# Alim.net
KiCad netlist of a schematic drawn in Altium Designer
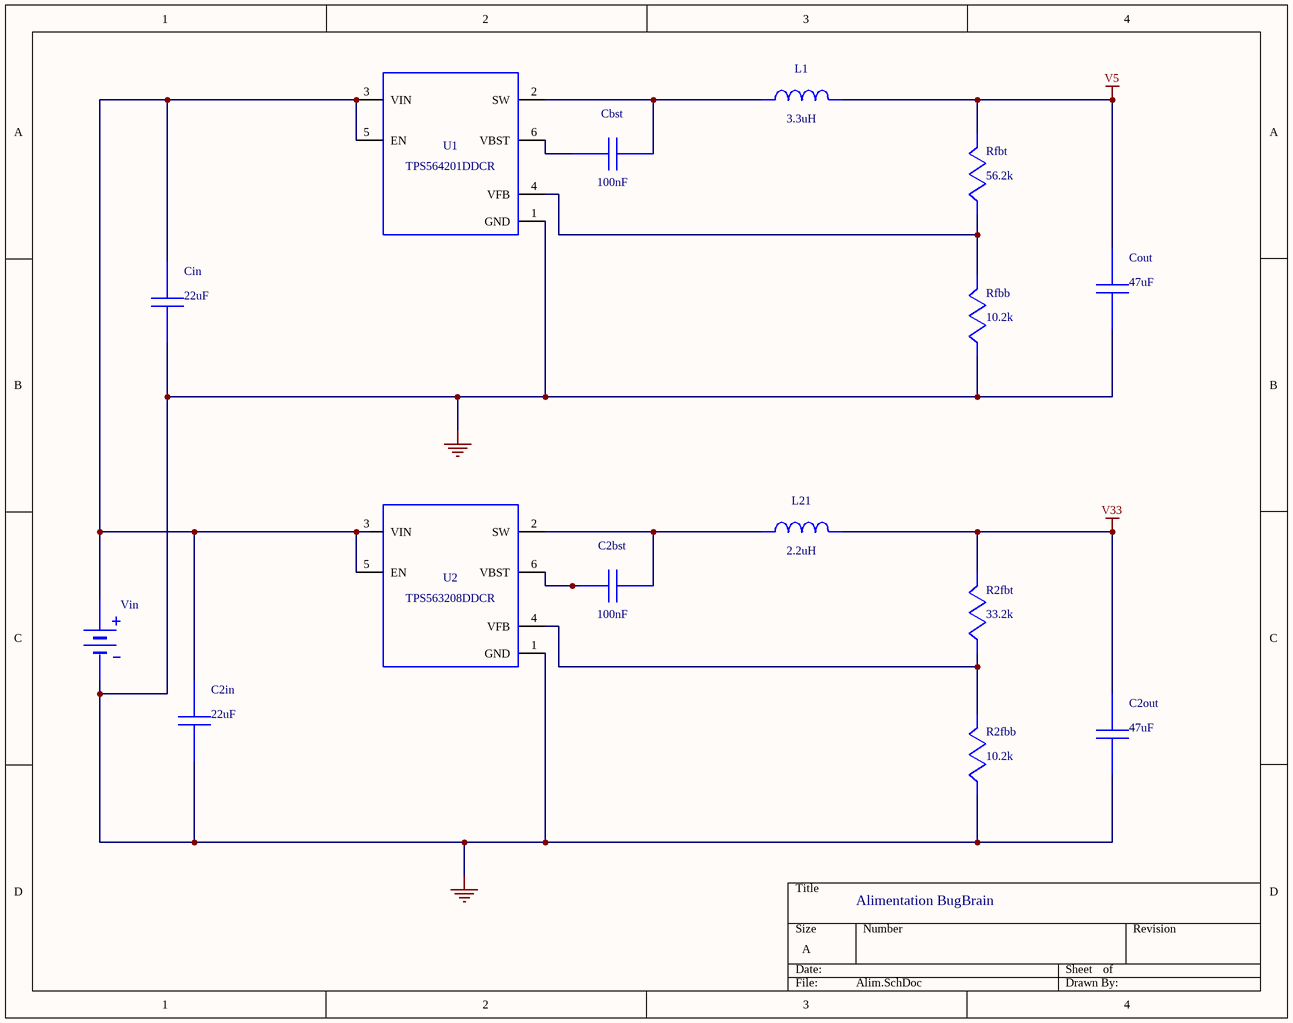
[diagram p0: Alim.SchDoc]

(export (version "E")
  (design (tool "Eeschema 10.0.6"))
  (components
    (comp (ref "C2bst")
      (value "100nF")
      (description "C0805C104K3RACTU")
      (libsource (lib "TI WEBENCH") (part "Cbst"))
    )
    (comp (ref "C2in")
      (value "22uF")
      (description "GRM32ER61E226KE1")
      (fields (field (name "MANUFACTURER PART NUMBER") "GRM32ER61E226KE15L"))
      (libsource (lib "TI WEBENCH") (part "Cin"))
    )
    (comp (ref "C2out")
      (value "47uF")
      (description "C3216X5R1E476M16")
      (fields (field (name "MANUFACTURER PART NUMBER") "C3216X5R1E476M160AC"))
      (libsource (lib "TI WEBENCH") (part "Cout"))
    )
    (comp (ref "Cbst")
      (value "100nF")
      (description "C0805C104K3RACTU")
      (libsource (lib "TI WEBENCH") (part "Cbst"))
    )
    (comp (ref "Cin")
      (value "22uF")
      (description "GRM32ER61E226KE1")
      (fields (field (name "MANUFACTURER PART NUMBER") "GRM32ER61E226KE15L"))
      (libsource (lib "TI WEBENCH") (part "Cin"))
    )
    (comp (ref "Cout")
      (value "47uF")
      (description "C3216X5R1E476M16")
      (fields (field (name "MANUFACTURER PART NUMBER") "C3216X5R1E476M160AC"))
      (libsource (lib "TI WEBENCH") (part "Cout"))
    )
    (comp (ref "L1")
      (value "3.3uH")
      (description "Unknown")
      (fields (field (name "MANUFACTURER PART NUMBER") "VLP8040T-3R3N"))
      (libsource (lib "TI WEBENCH") (part "L1"))
    )
    (comp (ref "L21")
      (value "2.2uH")
      (description "Unknown")
      (fields (field (name "MANUFACTURER PART NUMBER") "VLP8040T-2R2N"))
      (libsource (lib "TI WEBENCH") (part "L1"))
    )
    (comp (ref "R2fbb")
      (value "10.2k")
      (description "ERJ-6ENF1022V")
      (libsource (lib "TI WEBENCH") (part "Rfbb"))
    )
    (comp (ref "R2fbt")
      (value "33.2k")
      (description "CRCW040233K2FKED")
      (libsource (lib "TI WEBENCH") (part "Rfbt"))
    )
    (comp (ref "Rfbb")
      (value "10.2k")
      (description "ERJ-6ENF1022V")
      (libsource (lib "TI WEBENCH") (part "Rfbb"))
    )
    (comp (ref "Rfbt")
      (value "56.2k")
      (description "CRCW040256K2FKED")
      (libsource (lib "TI WEBENCH") (part "Rfbt"))
    )
    (comp (ref "U1")
      (value "TPS564201DDCR")
      (description "TPS564201DDCR - 5V")
      (fields (field (name "PACKAGEREFERENCE") "TPS564201DDCR"))
      (libsource (lib "TI WEBENCH") (part "U1"))
    )
    (comp (ref "U2")
      (value "TPS563208DDCR")
      (description "TPS563208DDCR 3.3V")
      (fields (field (name "PACKAGEREFERENCE") "TPS563208DDCR"))
      (libsource (lib "TI WEBENCH") (part "U1"))
    )
    (comp (ref "Vin") (value "WB_BATTERY") (libsource (lib "TI WEBENCH") (part "Vin")))
  )
  (nets
    (net (code "1") (name "0") (class "Default")
      (node (ref "C2in") (pin "2") (pinfunction "2_2") (pintype "passive"))
      (node (ref "C2out") (pin "2") (pinfunction "2_2") (pintype "passive"))
      (node (ref "Cin") (pin "2") (pinfunction "2_2") (pintype "passive"))
      (node (ref "Cout") (pin "2") (pinfunction "2_2") (pintype "passive"))
      (node (ref "R2fbb") (pin "2") (pinfunction "2_2") (pintype "passive"))
      (node (ref "Rfbb") (pin "2") (pinfunction "2_2") (pintype "passive"))
      (node (ref "U1") (pin "1") (pinfunction "GND_1") (pintype "power_in"))
      (node (ref "U2") (pin "1") (pinfunction "GND_1") (pintype "power_in"))
      (node (ref "Vin") (pin "2") (pinfunction "-_2") (pintype "passive"))
    )
    (net (code "2") (name "Net-(U1-EN)") (class "Default")
      (node (ref "C2in") (pin "1") (pinfunction "1_1") (pintype "passive"))
      (node (ref "Cin") (pin "1") (pinfunction "1_1") (pintype "passive"))
      (node (ref "U1") (pin "3") (pinfunction "VIN_3") (pintype "power_in"))
      (node (ref "U1") (pin "5") (pinfunction "EN_5") (pintype "passive"))
      (node (ref "U2") (pin "3") (pinfunction "VIN_3") (pintype "power_in"))
      (node (ref "U2") (pin "5") (pinfunction "EN_5") (pintype "passive"))
      (node (ref "Vin") (pin "1") (pinfunction "+_1") (pintype "passive"))
    )
    (net (code "3") (name "Net-(U1-SW)") (class "Default")
      (node (ref "Cbst") (pin "1") (pinfunction "1_1") (pintype "passive"))
      (node (ref "L1") (pin "1") (pinfunction "1_1") (pintype "passive"))
      (node (ref "U1") (pin "2") (pinfunction "SW_2") (pintype "power_in"))
    )
    (net (code "4") (name "Net-(U1-VBST)") (class "Default")
      (node (ref "Cbst") (pin "2") (pinfunction "2_2") (pintype "passive"))
      (node (ref "U1") (pin "6") (pinfunction "VBST_6") (pintype "power_in"))
    )
    (net (code "5") (name "Net-(U1-VFB)") (class "Default")
      (node (ref "Rfbb") (pin "1") (pinfunction "1_1") (pintype "passive"))
      (node (ref "Rfbt") (pin "2") (pinfunction "2_2") (pintype "passive"))
      (node (ref "U1") (pin "4") (pinfunction "VFB_4") (pintype "passive"))
    )
    (net (code "6") (name "Net-(U2-SW)") (class "Default")
      (node (ref "C2bst") (pin "1") (pinfunction "1_1") (pintype "passive"))
      (node (ref "L21") (pin "1") (pinfunction "1_1") (pintype "passive"))
      (node (ref "U2") (pin "2") (pinfunction "SW_2") (pintype "power_in"))
    )
    (net (code "7") (name "Net-(U2-VBST)") (class "Default")
      (node (ref "C2bst") (pin "2") (pinfunction "2_2") (pintype "passive"))
      (node (ref "U2") (pin "6") (pinfunction "VBST_6") (pintype "power_in"))
    )
    (net (code "8") (name "Net-(U2-VFB)") (class "Default")
      (node (ref "R2fbb") (pin "1") (pinfunction "1_1") (pintype "passive"))
      (node (ref "R2fbt") (pin "2") (pinfunction "2_2") (pintype "passive"))
      (node (ref "U2") (pin "4") (pinfunction "VFB_4") (pintype "passive"))
    )
    (net (code "9") (name "V5") (class "Default")
      (node (ref "Cout") (pin "1") (pinfunction "1_1") (pintype "passive"))
      (node (ref "L1") (pin "2") (pinfunction "2_2") (pintype "passive"))
      (node (ref "Rfbt") (pin "1") (pinfunction "1_1") (pintype "passive"))
    )
    (net (code "10") (name "V33") (class "Default")
      (node (ref "C2out") (pin "1") (pinfunction "1_1") (pintype "passive"))
      (node (ref "L21") (pin "2") (pinfunction "2_2") (pintype "passive"))
      (node (ref "R2fbt") (pin "1") (pinfunction "1_1") (pintype "passive"))
    )
  )
)
